# Output_Register.net
KiCad netlist of a schematic drawn in EasyEDA Pro
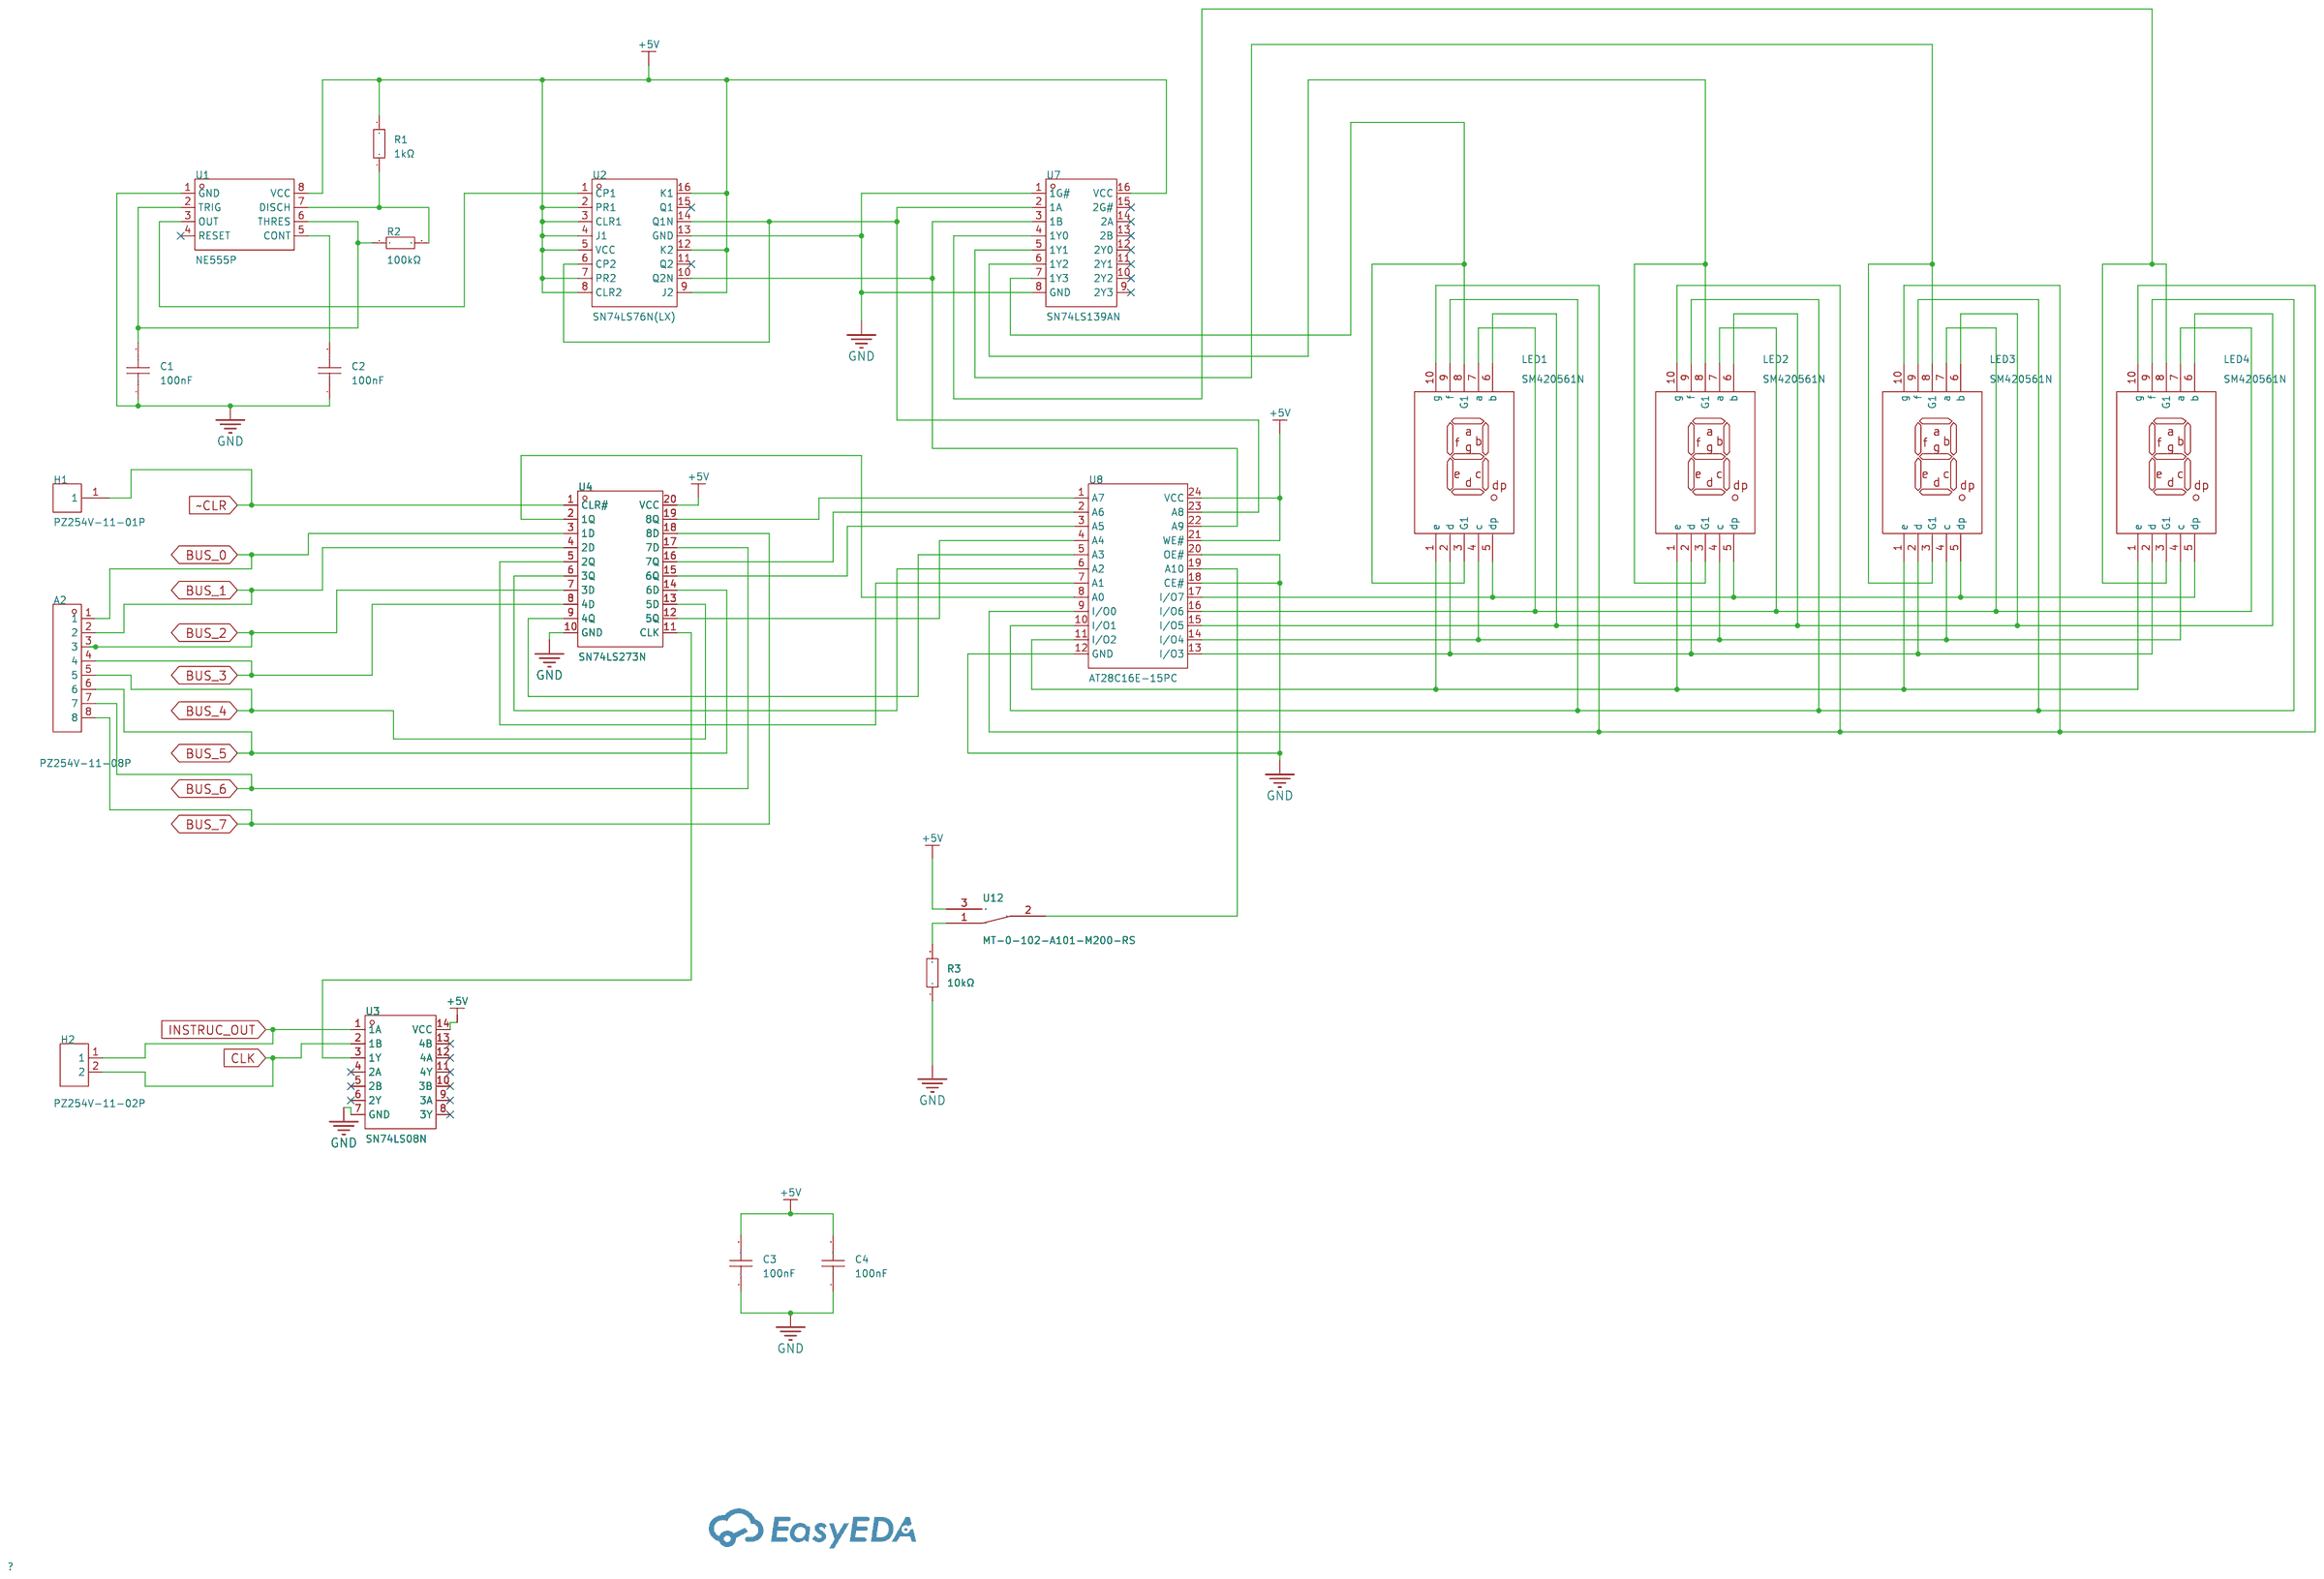
[diagram p0: schematic sheet]

(export (version "E")
  (design (tool "Eeschema 10.0.6"))
  (components
    (comp (ref "A2")
      (value "PZ254V-11-08P")
      (footprint "easyedapro:HDR-TH_8P-P2.54-V-M")
      (fields (field (name "Manufacturer") "XFCN(兴飞)"))
      (libsource (lib "easyedapro") (part "PZ254V-11-08P"))
    )
    (comp (ref "C1")
      (value "100nF")
      (footprint "easyedapro:CAP-TH_L8.5-W5.0-P5.00-D1.2")
      (fields (field (name "Manufacturer Part") "CT4-0805B104K500F3") (field (name "Manufacturer") "FH(风华)"))
      (libsource (lib "easyedapro") (part "CT4-0805B104K500F3"))
    )
    (comp (ref "C2")
      (value "100nF")
      (footprint "easyedapro:CAP-TH_L8.5-W5.0-P5.00-D1.2")
      (fields (field (name "Manufacturer Part") "CT4-0805B104K500F3") (field (name "Manufacturer") "FH(风华)"))
      (libsource (lib "easyedapro") (part "CT4-0805B104K500F3"))
    )
    (comp (ref "C3")
      (value "100nF")
      (footprint "easyedapro:CAP-TH_L8.5-W5.0-P5.00-D1.2")
      (fields (field (name "Manufacturer Part") "CT4-0805B104K500F3") (field (name "Manufacturer") "FH(风华)"))
      (libsource (lib "easyedapro") (part "CT4-0805B104K500F3"))
    )
    (comp (ref "C4")
      (value "100nF")
      (footprint "easyedapro:CAP-TH_L8.5-W5.0-P5.00-D1.2")
      (fields (field (name "Manufacturer Part") "CT4-0805B104K500F3") (field (name "Manufacturer") "FH(风华)"))
      (libsource (lib "easyedapro") (part "CT4-0805B104K500F3"))
    )
    (comp (ref "H1")
      (value "PZ254V-11-01P")
      (footprint "easyedapro:HDR-TH_1P-P2.54-V-M")
      (fields (field (name "Manufacturer") "XFCN(兴飞)"))
      (libsource (lib "easyedapro") (part "PZ254V-11-01P"))
    )
    (comp (ref "H2")
      (value "PZ254V-11-02P")
      (footprint "easyedapro:HDR-TH_2P-P2.54-V-M")
      (fields (field (name "Manufacturer") "XFCN(兴飞)"))
      (libsource (lib "easyedapro") (part "PZ254V-11-02P"))
    )
    (comp (ref "LED1")
      (value "SM420561N")
      (footprint "easyedapro:LED-SEG-TH_10P-L12.7-W19.0-P2.54-S15.24-BL")
      (fields (field (name "Manufacturer") "ARKLED(方舟)"))
      (libsource (lib "easyedapro") (part "SM420561N"))
    )
    (comp (ref "LED2")
      (value "SM420561N")
      (footprint "easyedapro:LED-SEG-TH_10P-L12.7-W19.0-P2.54-S15.24-BL")
      (fields (field (name "Manufacturer") "ARKLED(方舟)"))
      (libsource (lib "easyedapro") (part "SM420561N"))
    )
    (comp (ref "LED3")
      (value "SM420561N")
      (footprint "easyedapro:LED-SEG-TH_10P-L12.7-W19.0-P2.54-S15.24-BL")
      (fields (field (name "Manufacturer") "ARKLED(方舟)"))
      (libsource (lib "easyedapro") (part "SM420561N"))
    )
    (comp (ref "LED4")
      (value "SM420561N")
      (footprint "easyedapro:LED-SEG-TH_10P-L12.7-W19.0-P2.54-S15.24-BL")
      (fields (field (name "Manufacturer") "ARKLED(方舟)"))
      (libsource (lib "easyedapro") (part "SM420561N"))
    )
    (comp (ref "R1")
      (value "1kΩ")
      (footprint "easyedapro:R_AXIAL-0.4")
      (libsource (lib "easyedapro") (part "Res"))
    )
    (comp (ref "R2")
      (value "100kΩ")
      (footprint "easyedapro:R_AXIAL-0.4")
      (libsource (lib "easyedapro") (part "Res"))
    )
    (comp (ref "R3")
      (value "10kΩ")
      (footprint "easyedapro:R_AXIAL-0.4")
      (libsource (lib "easyedapro") (part "Res"))
    )
    (comp (ref "U1")
      (value "NE555P")
      (footprint "easyedapro:DIP-8_L9.8-W6.6-P2.54-LS7.6-BL")
      (fields (field (name "Manufacturer") "TI(德州仪器)"))
      (libsource (lib "easyedapro") (part "NE555P"))
    )
    (comp (ref "U2")
      (value "SN74LS76N(LX)")
      (footprint "easyedapro:PDIP-16_L19.3-W6.4-P2.54-LS7.94-BL")
      (fields (field (name "Manufacturer") "LX(灵星芯微)"))
      (libsource (lib "easyedapro") (part "SN74LS76N(LX)"))
    )
    (comp (ref "U3")
      (value "SN74LS08N")
      (footprint "easyedapro:PDIP-14_L19.3-W6.4-P2.54-LS7.9-BL-1")
      (fields (field (name "Manufacturer") "TI(德州仪器)"))
      (libsource (lib "easyedapro") (part "SN74LS08N"))
    )
    (comp (ref "U4")
      (value "SN74LS273N")
      (footprint "easyedapro:PDIP-20_L25.4-W6.4-P2.54-LS7.6-BL")
      (fields (field (name "Manufacturer") "TI(德州仪器)"))
      (libsource (lib "easyedapro") (part "SN74LS273N"))
    )
    (comp (ref "U7")
      (value "SN74LS139AN")
      (footprint "easyedapro:PDIP-16_L19.3-W6.4-P2.54-LS7.9-BL")
      (fields (field (name "Manufacturer") "TI(德州仪器)"))
      (libsource (lib "easyedapro") (part "SN74LS139AN"))
    )
    (comp (ref "U8")
      (value "AT28C16E-15PC")
      (footprint "easyedapro:PDIP-24_L31.0-W13.5-P2.54-LS15.2-BL")
      (fields (field (name "Manufacturer") "MICROCHIP(美国微芯)"))
      (libsource (lib "easyedapro") (part "AT28C16E-15PC"))
    )
    (comp (ref "U12")
      (value "MT-0-102-A101-M200-RS")
      (footprint "easyedapro:SW-TH_MT-0-103-A101-M200-RS")
      (fields (field (name "Manufacturer") "YUEN FUNG(源丰)"))
      (libsource (lib "easyedapro") (part "MT-0-102-A101-M200-RS+PJ"))
    )
  )
  (nets
    (net (code "1") (name "+5V") (class "Default")
      (node (ref "C3") (pin "2") (pinfunction "2_2") (pintype "unspecified"))
      (node (ref "C4") (pin "2") (pinfunction "2_2") (pintype "unspecified"))
      (node (ref "R1") (pin "2") (pinfunction "2_2") (pintype "input"))
      (node (ref "U1") (pin "8") (pinfunction "VCC_8") (pintype "input"))
      (node (ref "U12") (pin "3") (pinfunction "3_3") (pintype "unspecified"))
      (node (ref "U2") (pin "12") (pinfunction "K2_12") (pintype "unspecified"))
      (node (ref "U2") (pin "16") (pinfunction "K1_16") (pintype "unspecified"))
      (node (ref "U2") (pin "2") (pinfunction "PR1_2") (pintype "unspecified"))
      (node (ref "U2") (pin "3") (pinfunction "CLR1_3") (pintype "unspecified"))
      (node (ref "U2") (pin "4") (pinfunction "J1_4") (pintype "unspecified"))
      (node (ref "U2") (pin "5") (pinfunction "VCC_5") (pintype "unspecified"))
      (node (ref "U2") (pin "7") (pinfunction "PR2_7") (pintype "unspecified"))
      (node (ref "U2") (pin "8") (pinfunction "CLR2_8") (pintype "unspecified"))
      (node (ref "U2") (pin "9") (pinfunction "J2_9") (pintype "unspecified"))
      (node (ref "U3") (pin "14") (pinfunction "VCC_14") (pintype "unspecified"))
      (node (ref "U4") (pin "20") (pinfunction "VCC_20") (pintype "unspecified"))
      (node (ref "U7") (pin "16") (pinfunction "VCC_16") (pintype "input"))
      (node (ref "U8") (pin "21") (pinfunction "WE#_21") (pintype "unspecified"))
      (node (ref "U8") (pin "24") (pinfunction "VCC_24") (pintype "unspecified"))
    )
    (net (code "2") (name "BUS_0") (class "Default")
      (node (ref "A2") (pin "1") (pinfunction "1_1") (pintype "unspecified"))
      (node (ref "U4") (pin "3") (pinfunction "1D_3") (pintype "unspecified"))
    )
    (net (code "3") (name "BUS_1") (class "Default")
      (node (ref "A2") (pin "2") (pinfunction "2_2") (pintype "unspecified"))
      (node (ref "U4") (pin "4") (pinfunction "2D_4") (pintype "unspecified"))
    )
    (net (code "4") (name "BUS_2") (class "Default")
      (node (ref "A2") (pin "3") (pinfunction "3_3") (pintype "unspecified"))
      (node (ref "U4") (pin "7") (pinfunction "3D_7") (pintype "unspecified"))
    )
    (net (code "5") (name "BUS_3") (class "Default")
      (node (ref "A2") (pin "4") (pinfunction "4_4") (pintype "unspecified"))
      (node (ref "U4") (pin "8") (pinfunction "4D_8") (pintype "unspecified"))
    )
    (net (code "6") (name "BUS_4") (class "Default")
      (node (ref "A2") (pin "5") (pinfunction "5_5") (pintype "unspecified"))
      (node (ref "U4") (pin "13") (pinfunction "5D_13") (pintype "unspecified"))
    )
    (net (code "7") (name "BUS_5") (class "Default")
      (node (ref "A2") (pin "6") (pinfunction "6_6") (pintype "unspecified"))
      (node (ref "U4") (pin "14") (pinfunction "6D_14") (pintype "unspecified"))
    )
    (net (code "8") (name "BUS_6") (class "Default")
      (node (ref "A2") (pin "7") (pinfunction "7_7") (pintype "unspecified"))
      (node (ref "U4") (pin "17") (pinfunction "7D_17") (pintype "unspecified"))
    )
    (net (code "9") (name "BUS_7") (class "Default")
      (node (ref "A2") (pin "8") (pinfunction "8_8") (pintype "unspecified"))
      (node (ref "U4") (pin "18") (pinfunction "8D_18") (pintype "unspecified"))
    )
    (net (code "10") (name "CLK") (class "Default")
      (node (ref "H2") (pin "2") (pinfunction "2_2") (pintype "unspecified"))
      (node (ref "U3") (pin "2") (pinfunction "1B_2") (pintype "unspecified"))
    )
    (net (code "11") (name "GND") (class "Default")
      (node (ref "C1") (pin "1") (pinfunction "1_1") (pintype "unspecified"))
      (node (ref "C2") (pin "1") (pinfunction "1_1") (pintype "unspecified"))
      (node (ref "C3") (pin "1") (pinfunction "1_1") (pintype "unspecified"))
      (node (ref "C4") (pin "1") (pinfunction "1_1") (pintype "unspecified"))
      (node (ref "R3") (pin "1") (pinfunction "1_1") (pintype "input"))
      (node (ref "U1") (pin "1") (pinfunction "GND_1") (pintype "input"))
      (node (ref "U2") (pin "13") (pinfunction "GND_13") (pintype "unspecified"))
      (node (ref "U3") (pin "7") (pinfunction "GND_7") (pintype "unspecified"))
      (node (ref "U4") (pin "10") (pinfunction "GND_10") (pintype "unspecified"))
      (node (ref "U7") (pin "1") (pinfunction "1G#_1") (pintype "input"))
      (node (ref "U7") (pin "8") (pinfunction "GND_8") (pintype "input"))
      (node (ref "U8") (pin "12") (pinfunction "GND_12") (pintype "unspecified"))
      (node (ref "U8") (pin "18") (pinfunction "CE#_18") (pintype "unspecified"))
      (node (ref "U8") (pin "20") (pinfunction "OE#_20") (pintype "unspecified"))
    )
    (net (code "12") (name "INSTRUC_OUT") (class "Default")
      (node (ref "H2") (pin "1") (pinfunction "1_1") (pintype "unspecified"))
      (node (ref "U3") (pin "1") (pinfunction "1A_1") (pintype "unspecified"))
    )
    (net (code "13") (name "Net-(LED1-a)") (class "Default")
      (node (ref "LED1") (pin "7") (pinfunction "a_7") (pintype "input"))
      (node (ref "LED2") (pin "7") (pinfunction "a_7") (pintype "input"))
      (node (ref "LED3") (pin "7") (pinfunction "a_7") (pintype "input"))
      (node (ref "LED4") (pin "7") (pinfunction "a_7") (pintype "input"))
      (node (ref "U8") (pin "16") (pinfunction "I/O6_16") (pintype "unspecified"))
    )
    (net (code "14") (name "Net-(LED1-b)") (class "Default")
      (node (ref "LED1") (pin "6") (pinfunction "b_6") (pintype "input"))
      (node (ref "LED2") (pin "6") (pinfunction "b_6") (pintype "input"))
      (node (ref "LED3") (pin "6") (pinfunction "b_6") (pintype "input"))
      (node (ref "LED4") (pin "6") (pinfunction "b_6") (pintype "input"))
      (node (ref "U8") (pin "15") (pinfunction "I/O5_15") (pintype "unspecified"))
    )
    (net (code "15") (name "Net-(LED1-c)") (class "Default")
      (node (ref "LED1") (pin "4") (pinfunction "c_4") (pintype "input"))
      (node (ref "LED2") (pin "4") (pinfunction "c_4") (pintype "input"))
      (node (ref "LED3") (pin "4") (pinfunction "c_4") (pintype "input"))
      (node (ref "LED4") (pin "4") (pinfunction "c_4") (pintype "input"))
      (node (ref "U8") (pin "14") (pinfunction "I/O4_14") (pintype "unspecified"))
    )
    (net (code "16") (name "Net-(LED1-d)") (class "Default")
      (node (ref "LED1") (pin "2") (pinfunction "d_2") (pintype "input"))
      (node (ref "LED2") (pin "2") (pinfunction "d_2") (pintype "input"))
      (node (ref "LED3") (pin "2") (pinfunction "d_2") (pintype "input"))
      (node (ref "LED4") (pin "2") (pinfunction "d_2") (pintype "input"))
      (node (ref "U8") (pin "13") (pinfunction "I/O3_13") (pintype "unspecified"))
    )
    (net (code "17") (name "Net-(LED1-dp)") (class "Default")
      (node (ref "LED1") (pin "5") (pinfunction "dp_5") (pintype "input"))
      (node (ref "LED2") (pin "5") (pinfunction "dp_5") (pintype "input"))
      (node (ref "LED3") (pin "5") (pinfunction "dp_5") (pintype "input"))
      (node (ref "LED4") (pin "5") (pinfunction "dp_5") (pintype "input"))
      (node (ref "U8") (pin "17") (pinfunction "I/O7_17") (pintype "unspecified"))
    )
    (net (code "18") (name "Net-(LED1-e)") (class "Default")
      (node (ref "LED1") (pin "1") (pinfunction "e_1") (pintype "input"))
      (node (ref "LED2") (pin "1") (pinfunction "e_1") (pintype "input"))
      (node (ref "LED3") (pin "1") (pinfunction "e_1") (pintype "input"))
      (node (ref "LED4") (pin "1") (pinfunction "e_1") (pintype "input"))
      (node (ref "U8") (pin "11") (pinfunction "I/O2_11") (pintype "unspecified"))
    )
    (net (code "19") (name "Net-(LED1-f)") (class "Default")
      (node (ref "LED1") (pin "9") (pinfunction "f_9") (pintype "input"))
      (node (ref "LED2") (pin "9") (pinfunction "f_9") (pintype "input"))
      (node (ref "LED3") (pin "9") (pinfunction "f_9") (pintype "input"))
      (node (ref "LED4") (pin "9") (pinfunction "f_9") (pintype "input"))
      (node (ref "U8") (pin "10") (pinfunction "I/O1_10") (pintype "unspecified"))
    )
    (net (code "20") (name "Net-(LED1-g)") (class "Default")
      (node (ref "LED1") (pin "10") (pinfunction "g_10") (pintype "input"))
      (node (ref "LED2") (pin "10") (pinfunction "g_10") (pintype "input"))
      (node (ref "LED3") (pin "10") (pinfunction "g_10") (pintype "input"))
      (node (ref "LED4") (pin "10") (pinfunction "g_10") (pintype "input"))
      (node (ref "U8") (pin "9") (pinfunction "I/O0_9") (pintype "unspecified"))
    )
    (net (code "21") (name "Net-(R3-Pad2)") (class "Default")
      (node (ref "R3") (pin "2") (pinfunction "2_2") (pintype "input"))
      (node (ref "U12") (pin "1") (pinfunction "1_1") (pintype "unspecified"))
    )
    (net (code "22") (name "Net-(U1-CONT)") (class "Default")
      (node (ref "C2") (pin "2") (pinfunction "2_2") (pintype "unspecified"))
      (node (ref "U1") (pin "5") (pinfunction "CONT_5") (pintype "input"))
    )
    (net (code "23") (name "Net-(U1-DISCH)") (class "Default")
      (node (ref "R1") (pin "1") (pinfunction "1_1") (pintype "input"))
      (node (ref "R2") (pin "2") (pinfunction "2_2") (pintype "input"))
      (node (ref "U1") (pin "7") (pinfunction "DISCH_7") (pintype "input"))
    )
    (net (code "24") (name "Net-(U1-OUT)") (class "Default")
      (node (ref "U1") (pin "3") (pinfunction "OUT_3") (pintype "input"))
      (node (ref "U2") (pin "1") (pinfunction "CP1_1") (pintype "unspecified"))
    )
    (net (code "25") (name "Net-(U1-THRES)") (class "Default")
      (node (ref "C1") (pin "2") (pinfunction "2_2") (pintype "unspecified"))
      (node (ref "R2") (pin "1") (pinfunction "1_1") (pintype "input"))
      (node (ref "U1") (pin "2") (pinfunction "TRIG_2") (pintype "input"))
      (node (ref "U1") (pin "6") (pinfunction "THRES_6") (pintype "input"))
    )
    (net (code "26") (name "Net-(U2-CP2)") (class "Default")
      (node (ref "U2") (pin "14") (pinfunction "Q1N_14") (pintype "unspecified"))
      (node (ref "U2") (pin "6") (pinfunction "CP2_6") (pintype "unspecified"))
      (node (ref "U7") (pin "2") (pinfunction "1A_2") (pintype "input"))
      (node (ref "U8") (pin "23") (pinfunction "A8_23") (pintype "unspecified"))
    )
    (net (code "27") (name "Net-(U2-Q2N)") (class "Default")
      (node (ref "U2") (pin "10") (pinfunction "Q2N_10") (pintype "unspecified"))
      (node (ref "U7") (pin "3") (pinfunction "1B_3") (pintype "input"))
      (node (ref "U8") (pin "22") (pinfunction "A9_22") (pintype "unspecified"))
    )
    (net (code "28") (name "Net-(U3-1Y)") (class "Default")
      (node (ref "U3") (pin "3") (pinfunction "1Y_3") (pintype "unspecified"))
      (node (ref "U4") (pin "11") (pinfunction "CLK_11") (pintype "unspecified"))
    )
    (net (code "29") (name "Net-(U4-1Q)") (class "Default")
      (node (ref "U4") (pin "2") (pinfunction "1Q_2") (pintype "unspecified"))
      (node (ref "U8") (pin "8") (pinfunction "A0_8") (pintype "unspecified"))
    )
    (net (code "30") (name "Net-(U4-2Q)") (class "Default")
      (node (ref "U4") (pin "5") (pinfunction "2Q_5") (pintype "unspecified"))
      (node (ref "U8") (pin "7") (pinfunction "A1_7") (pintype "unspecified"))
    )
    (net (code "31") (name "Net-(U4-3Q)") (class "Default")
      (node (ref "U4") (pin "6") (pinfunction "3Q_6") (pintype "unspecified"))
      (node (ref "U8") (pin "6") (pinfunction "A2_6") (pintype "unspecified"))
    )
    (net (code "32") (name "Net-(U4-4Q)") (class "Default")
      (node (ref "U4") (pin "9") (pinfunction "4Q_9") (pintype "unspecified"))
      (node (ref "U8") (pin "5") (pinfunction "A3_5") (pintype "unspecified"))
    )
    (net (code "33") (name "Net-(U4-5Q)") (class "Default")
      (node (ref "U4") (pin "12") (pinfunction "5Q_12") (pintype "unspecified"))
      (node (ref "U8") (pin "4") (pinfunction "A4_4") (pintype "unspecified"))
    )
    (net (code "34") (name "Net-(U4-6Q)") (class "Default")
      (node (ref "U4") (pin "15") (pinfunction "6Q_15") (pintype "unspecified"))
      (node (ref "U8") (pin "3") (pinfunction "A5_3") (pintype "unspecified"))
    )
    (net (code "35") (name "Net-(U4-7Q)") (class "Default")
      (node (ref "U4") (pin "16") (pinfunction "7Q_16") (pintype "unspecified"))
      (node (ref "U8") (pin "2") (pinfunction "A6_2") (pintype "unspecified"))
    )
    (net (code "36") (name "Net-(U4-8Q)") (class "Default")
      (node (ref "U4") (pin "19") (pinfunction "8Q_19") (pintype "unspecified"))
      (node (ref "U8") (pin "1") (pinfunction "A7_1") (pintype "unspecified"))
    )
    (net (code "37") (name "Net-(U7-1Y0)") (class "Default")
      (node (ref "LED4") (pin "3") (pinfunction "G1_3") (pintype "input"))
      (node (ref "LED4") (pin "8") (pinfunction "G1_8") (pintype "input"))
      (node (ref "U7") (pin "4") (pinfunction "1Y0_4") (pintype "input"))
    )
    (net (code "38") (name "Net-(U7-1Y1)") (class "Default")
      (node (ref "LED3") (pin "3") (pinfunction "G1_3") (pintype "input"))
      (node (ref "LED3") (pin "8") (pinfunction "G1_8") (pintype "input"))
      (node (ref "U7") (pin "5") (pinfunction "1Y1_5") (pintype "input"))
    )
    (net (code "39") (name "Net-(U7-1Y2)") (class "Default")
      (node (ref "LED2") (pin "3") (pinfunction "G1_3") (pintype "input"))
      (node (ref "LED2") (pin "8") (pinfunction "G1_8") (pintype "input"))
      (node (ref "U7") (pin "6") (pinfunction "1Y2_6") (pintype "input"))
    )
    (net (code "40") (name "Net-(U7-1Y3)") (class "Default")
      (node (ref "LED1") (pin "3") (pinfunction "G1_3") (pintype "input"))
      (node (ref "LED1") (pin "8") (pinfunction "G1_8") (pintype "input"))
      (node (ref "U7") (pin "7") (pinfunction "1Y3_7") (pintype "input"))
    )
    (net (code "41") (name "Net-(U8-A10)") (class "Default")
      (node (ref "U12") (pin "2") (pinfunction "2_2") (pintype "unspecified"))
      (node (ref "U8") (pin "19") (pinfunction "A10_19") (pintype "unspecified"))
    )
    (net (code "42") (name "unconnected-(U1-RESET-Pad4)") (class "Default")
      (node (ref "U1") (pin "4") (pinfunction "RESET_4") (pintype "input+no_connect"))
    )
    (net (code "43") (name "unconnected-(U2-Q1-Pad15)") (class "Default")
      (node (ref "U2") (pin "15") (pinfunction "Q1_15") (pintype "unspecified+no_connect"))
    )
    (net (code "44") (name "unconnected-(U2-Q2-Pad11)") (class "Default")
      (node (ref "U2") (pin "11") (pinfunction "Q2_11") (pintype "unspecified+no_connect"))
    )
    (net (code "45") (name "unconnected-(U3-2A-Pad4)") (class "Default")
      (node (ref "U3") (pin "4") (pinfunction "2A_4") (pintype "unspecified+no_connect"))
    )
    (net (code "46") (name "unconnected-(U3-2B-Pad5)") (class "Default")
      (node (ref "U3") (pin "5") (pinfunction "2B_5") (pintype "unspecified+no_connect"))
    )
    (net (code "47") (name "unconnected-(U3-2Y-Pad6)") (class "Default")
      (node (ref "U3") (pin "6") (pinfunction "2Y_6") (pintype "unspecified+no_connect"))
    )
    (net (code "48") (name "unconnected-(U3-3A-Pad9)") (class "Default")
      (node (ref "U3") (pin "9") (pinfunction "3A_9") (pintype "unspecified+no_connect"))
    )
    (net (code "49") (name "unconnected-(U3-3B-Pad10)") (class "Default")
      (node (ref "U3") (pin "10") (pinfunction "3B_10") (pintype "unspecified+no_connect"))
    )
    (net (code "50") (name "unconnected-(U3-3Y-Pad8)") (class "Default")
      (node (ref "U3") (pin "8") (pinfunction "3Y_8") (pintype "unspecified+no_connect"))
    )
    (net (code "51") (name "unconnected-(U3-4A-Pad12)") (class "Default")
      (node (ref "U3") (pin "12") (pinfunction "4A_12") (pintype "unspecified+no_connect"))
    )
    (net (code "52") (name "unconnected-(U3-4B-Pad13)") (class "Default")
      (node (ref "U3") (pin "13") (pinfunction "4B_13") (pintype "unspecified+no_connect"))
    )
    (net (code "53") (name "unconnected-(U3-4Y-Pad11)") (class "Default")
      (node (ref "U3") (pin "11") (pinfunction "4Y_11") (pintype "unspecified+no_connect"))
    )
    (net (code "54") (name "unconnected-(U7-2A-Pad14)") (class "Default")
      (node (ref "U7") (pin "14") (pinfunction "2A_14") (pintype "input+no_connect"))
    )
    (net (code "55") (name "unconnected-(U7-2B-Pad13)") (class "Default")
      (node (ref "U7") (pin "13") (pinfunction "2B_13") (pintype "input+no_connect"))
    )
    (net (code "56") (name "unconnected-(U7-2G#-Pad15)") (class "Default")
      (node (ref "U7") (pin "15") (pinfunction "2G#_15") (pintype "input+no_connect"))
    )
    (net (code "57") (name "unconnected-(U7-2Y0-Pad12)") (class "Default")
      (node (ref "U7") (pin "12") (pinfunction "2Y0_12") (pintype "input+no_connect"))
    )
    (net (code "58") (name "unconnected-(U7-2Y1-Pad11)") (class "Default")
      (node (ref "U7") (pin "11") (pinfunction "2Y1_11") (pintype "input+no_connect"))
    )
    (net (code "59") (name "unconnected-(U7-2Y2-Pad10)") (class "Default")
      (node (ref "U7") (pin "10") (pinfunction "2Y2_10") (pintype "input+no_connect"))
    )
    (net (code "60") (name "unconnected-(U7-2Y3-Pad9)") (class "Default")
      (node (ref "U7") (pin "9") (pinfunction "2Y3_9") (pintype "input+no_connect"))
    )
    (net (code "61") (name "~CLR") (class "Default")
      (node (ref "H1") (pin "1") (pinfunction "1_1") (pintype "unspecified"))
      (node (ref "U4") (pin "1") (pinfunction "CLR#_1") (pintype "unspecified"))
    )
  )
)
